# MainBoard_Motor1.net
KiCad netlist of a schematic drawn in Altium Designer
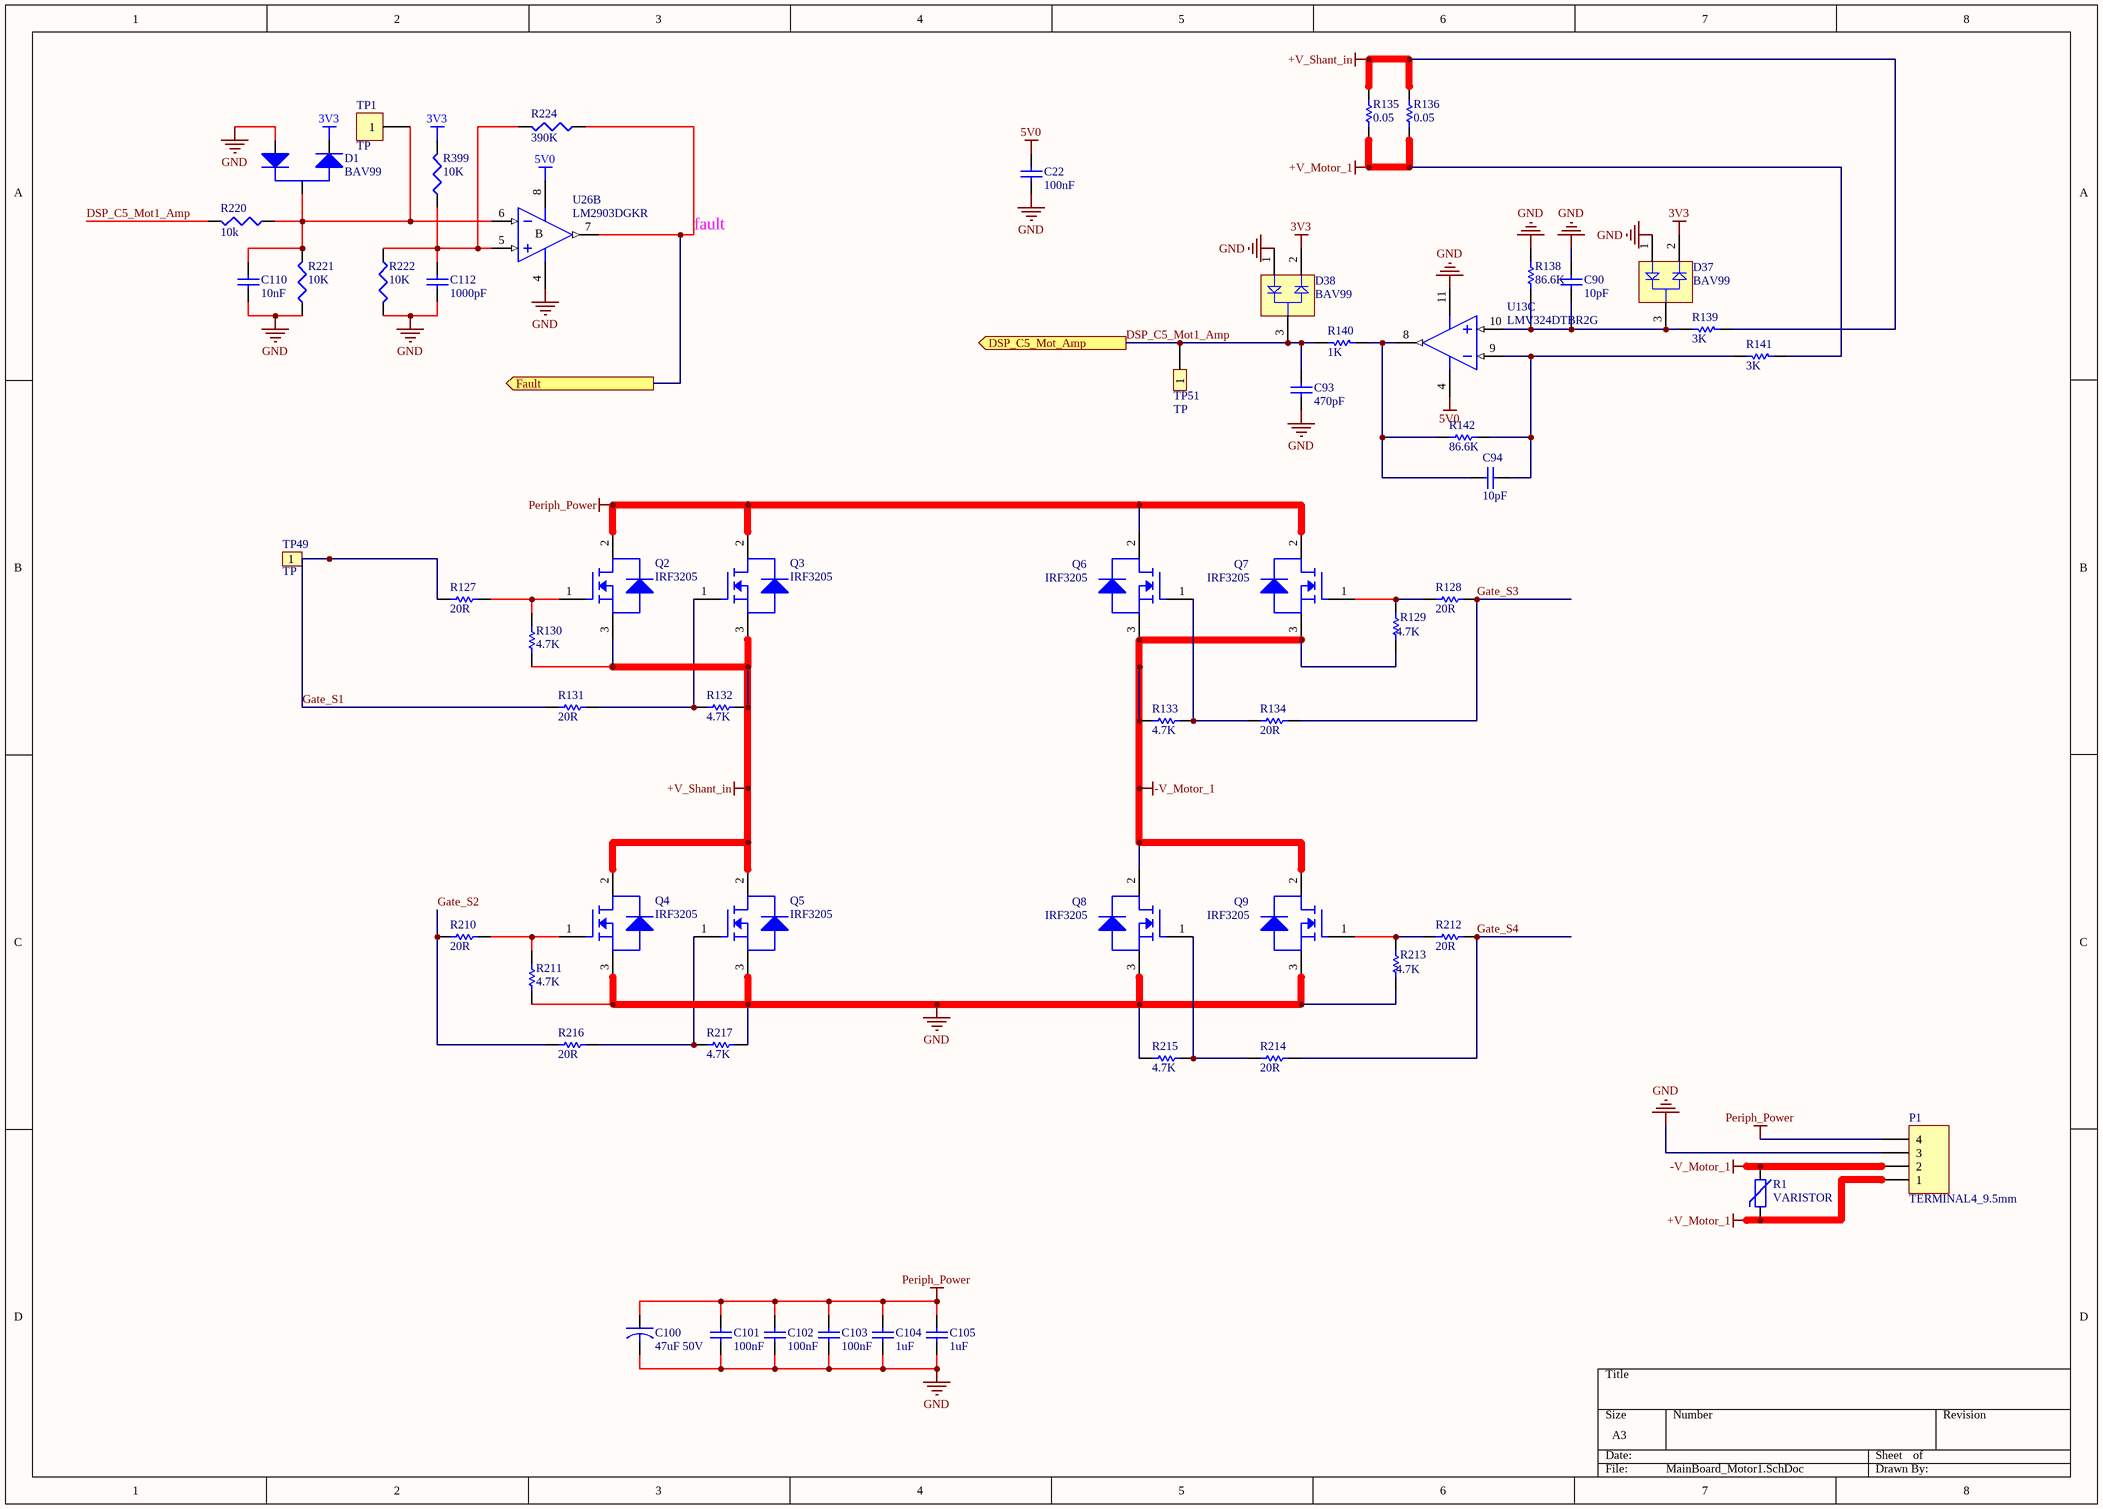
[diagram p0: MainBoard_Motor1.SchDoc]

(export (version "E")
  (design (tool "Eeschema 10.0.6"))
  (components
    (comp (ref "C22")
      (value "100nF")
      (footprint "EVIDC:C0603")
      (description "Ceramic Chip Capacitor - Standard")
      (fields
        (field (name "MANUFACTURER") "Yageo")
        (field (name "MFR PART NO") "CC0603KPX7R9BB104")
        (field (name "PUBLISHER") "Altium Limited")
      )
      (libsource (lib "KEMET Chip Capacitor") (part "C0402"))
    )
    (comp (ref "C90")
      (value "10pF")
      (footprint "EVIDC:C0603")
      (description "Cap_10pF_5%_C0G_50V_0603")
      (fields (field (name "MANUFACTURER") "Yageo") (field (name "MFR PART NO") "CC0603JRNPO9BN510"))
      (libsource (lib "EVIDC") (part "Cap_510pF_50V_0603"))
    )
    (comp (ref "C93")
      (value "470pF")
      (footprint "EVIDC:C0603")
      (description "Cap_470pF_5%_C0G_50V_0603")
      (fields (field (name "MFR PART NO") "CC0603JRNPO9BN471") (field (name "MANUFACTURER") "Yageo"))
      (libsource (lib "EVIDC") (part "Cap_470pF_50V_0603"))
    )
    (comp (ref "C94")
      (value "10pF")
      (footprint "C0603")
      (description "Cap_10pF_5%_C0G_50V_0603")
      (fields (field (name "MANUFACTURER") "Yageo") (field (name "MFR PART NO") "CC0603JRNPO9BN510"))
      (libsource (lib "EVIDC") (part "Cap_510pF_50V_0603"))
    )
    (comp (ref "C100")
      (value "47uF 50V")
      (footprint "RB-SGF-6.3MM")
      (description "Cap_47uF 50V_Pitch2.5mm")
      (fields (field (name "MFR PART NO") "ERS1HM470E11OT") (field (name "MANUFACTURER") "AIHUA"))
      (libsource (lib "EVIDC") (part "Cap_47uF 50V_EL_6.3mm"))
    )
    (comp (ref "C101")
      (value "100nF")
      (footprint "EVIDC:C0805")
      (description "Cap_100nF_5%_X7R_50V_0805")
      (fields (field (name "MANUFACTURER") "VISHAY") (field (name "MFR PART NO") "VJ0805Y104JXAAT"))
      (libsource (lib "EVIDC") (part "Cap_100nF_50V_0805"))
    )
    (comp (ref "C102")
      (value "100nF")
      (footprint "EVIDC:C0805")
      (description "Cap_100nF_5%_X7R_50V_0805")
      (fields (field (name "MANUFACTURER") "VISHAY") (field (name "MFR PART NO") "VJ0805Y104JXAAT"))
      (libsource (lib "EVIDC") (part "Cap_100nF_50V_0805"))
    )
    (comp (ref "C103")
      (value "100nF")
      (footprint "EVIDC:C0805")
      (description "Cap_100nF_5%_X7R_50V_0805")
      (fields (field (name "MANUFACTURER") "VISHAY") (field (name "MFR PART NO") "VJ0805Y104JXAAT"))
      (libsource (lib "EVIDC") (part "Cap_100nF_50V_0805"))
    )
    (comp (ref "C104")
      (value "1uF")
      (footprint "EVIDC:C0805")
      (description "Cap_1uF_20%_X5R_50V_0805")
      (fields (field (name "MFR PART NO") "UMK212BJ105MGHT") (field (name "MANUFACTURER") "Taiyo Yuden"))
      (libsource (lib "EVIDC") (part "Cap_1uF_50V_0805"))
    )
    (comp (ref "C105")
      (value "1uF")
      (footprint "EVIDC:C0805")
      (description "Cap_1uF_20%_X5R_50V_0805")
      (fields (field (name "MFR PART NO") "UMK212BJ105MGHT") (field (name "MANUFACTURER") "Taiyo Yuden"))
      (libsource (lib "EVIDC") (part "Cap_1uF_50V_0805"))
    )
    (comp (ref "C110")
      (value "10nF")
      (footprint "0603-C-PW")
      (description "CAP CER 10000PF 50V X7R 0603")
      (fields
        (field (name "MANUFACTURER") "Yageo")
        (field (name "MFR PART NO") "AC0603KPX7R9BB103")
        (field (name "PUBLISHER") "Altium Limited")
      )
      (libsource (lib "Miscellaneous Devices") (part "Cap"))
    )
    (comp (ref "C112")
      (value "1000pF")
      (footprint "0603-C-PW")
      (description "CAP CER 1000PF 50V X7R 0603")
      (fields
        (field (name "MANUFACTURER") "Yageo")
        (field (name "MFR PART NO") "CC0603KRX7R9BB102")
        (field (name "PUBLISHER") "Altium Limited")
      )
      (libsource (lib "Miscellaneous Devices") (part "Cap"))
    )
    (comp (ref "D1")
      (value "BAV99")
      (footprint "SOT-23-PW")
      (description "DIODE ARRAY GP 100V 215MA SOT23")
      (fields (field (name "MANUFACTURER") "Nexperia") (field (name "MFR PART NO") "BAV99,215"))
      (libsource (lib "PW232301036") (part "BAV99"))
    )
    (comp (ref "D37")
      (value "BAV99")
      (footprint "EVIDC:SOT-23")
      (description "Dِiode_BAV99_A7W_SOT23")
      (fields (field (name "MANUFACTURER") "Diode Incorporated") (field (name "MFR PART NO") "BAV99-7-F"))
      (libsource (lib "Infineon Transistor & Diode") (part "BAV99"))
    )
    (comp (ref "D38")
      (value "BAV99")
      (footprint "EVIDC:SOT-23")
      (description "Dِiode_BAV99_A7W_SOT23")
      (fields (field (name "MANUFACTURER") "Diode Incorporated") (field (name "MFR PART NO") "BAV99-7-F"))
      (libsource (lib "Infineon Transistor & Diode") (part "BAV99"))
    )
    (comp (ref "P1")
      (value "TERMINAL4_9.5mm")
      (footprint "Footprint_950322:Terminal 9.5mm_4")
      (description "T44-9.5mm_4")
      (fields (field (name "MANUFACTURER") "Cixi Kefa Elec") (field (name "MFR PART NO") "KF45C-9-5-4P"))
      (libsource (lib "SolarPanelCleaner_MainBoard_V1.1") (part "TERMINAL4_9.5mm"))
    )
    (comp (ref "Q2")
      (value "IRF3205")
      (footprint "2PH4888A00:TO-220")
      (description "MOSFET N-CHANNEL_ 55V_ TO-220")
      (fields (field (name "MANUFACTURER") "International Rectifier"))
      (libsource (lib "2PH4888A00") (part "MOS_IRF3205"))
    )
    (comp (ref "Q3")
      (value "IRF3205")
      (footprint "2PH4888A00:TO-220")
      (description "MOSFET N-CHANNEL_ 55V_ TO-220")
      (fields (field (name "MANUFACTURER") "International Rectifier"))
      (libsource (lib "2PH4888A00") (part "MOS_IRF3205"))
    )
    (comp (ref "Q4")
      (value "IRF3205")
      (footprint "2PH4888A00:TO-220")
      (description "MOSFET N-CHANNEL_ 55V_ TO-220")
      (fields (field (name "MANUFACTURER") "International Rectifier"))
      (libsource (lib "2PH4888A00") (part "MOS_IRF3205"))
    )
    (comp (ref "Q5")
      (value "IRF3205")
      (footprint "2PH4888A00:TO-220")
      (description "MOSFET N-CHANNEL_ 55V_ TO-220")
      (fields (field (name "MANUFACTURER") "International Rectifier"))
      (libsource (lib "2PH4888A00") (part "MOS_IRF3205"))
    )
    (comp (ref "Q6")
      (value "IRF3205")
      (footprint "2PH4888A00:TO-220")
      (description "MOSFET N-CHANNEL_ 55V_ TO-220")
      (fields (field (name "MANUFACTURER") "International Rectifier"))
      (libsource (lib "2PH4888A00") (part "MOS_IRF3205"))
    )
    (comp (ref "Q7")
      (value "IRF3205")
      (footprint "2PH4888A00:TO-220")
      (description "MOSFET N-CHANNEL_ 55V_ TO-220")
      (fields (field (name "MANUFACTURER") "International Rectifier"))
      (libsource (lib "2PH4888A00") (part "MOS_IRF3205"))
    )
    (comp (ref "Q8")
      (value "IRF3205")
      (footprint "2PH4888A00:TO-220")
      (description "MOSFET N-CHANNEL_ 55V_ TO-220")
      (fields (field (name "MANUFACTURER") "International Rectifier"))
      (libsource (lib "2PH4888A00") (part "MOS_IRF3205"))
    )
    (comp (ref "Q9")
      (value "IRF3205")
      (footprint "2PH4888A00:TO-220")
      (description "MOSFET N-CHANNEL_ 55V_ TO-220")
      (fields (field (name "MANUFACTURER") "International Rectifier"))
      (libsource (lib "2PH4888A00") (part "MOS_IRF3205"))
    )
    (comp (ref "R1")
      (value "VARISTOR")
      (footprint "2PH4888A00:VARISTOR")
      (description "35V 2cm")
      (fields (field (name "MANUFACTURER") "TDK Epcos") (field (name "MFR PART NO") "B72220S0350K101"))
      (libsource (lib "2PH4888A00") (part "VARISTOR"))
    )
    (comp (ref "R127")
      (value "20R")
      (footprint "EVIDC:R1206")
      (description "Res_20R_1%_0.25W_1206")
      (fields (field (name "MANUFACTURER") "Yageo") (field (name "MFR PART NO") "RC1206FR-0720RL"))
      (libsource (lib "EVIDC") (part "Res_20R_1206"))
    )
    (comp (ref "R128")
      (value "20R")
      (footprint "EVIDC:R1206")
      (description "Res_20R_1%_0.25W_1206")
      (fields (field (name "MANUFACTURER") "Yageo") (field (name "MFR PART NO") "RC1206FR-0720RL"))
      (libsource (lib "EVIDC") (part "Res_20R_1206"))
    )
    (comp (ref "R129")
      (value "4.7K")
      (footprint "EVIDC:R0805")
      (description "Res_4.7K_1%_0805")
      (fields (field (name "MANUFACTURER") "Yageo") (field (name "MFR PART NO") "RC0805FR-074K7L"))
      (libsource (lib "EVIDC") (part "Res_4.7K_0805"))
    )
    (comp (ref "R130")
      (value "4.7K")
      (footprint "EVIDC:R0805")
      (description "Res_4.7K_1%_0805")
      (fields (field (name "MANUFACTURER") "Yageo") (field (name "MFR PART NO") "RC0805FR-074K7L"))
      (libsource (lib "EVIDC") (part "Res_4.7K_0805"))
    )
    (comp (ref "R131")
      (value "20R")
      (footprint "EVIDC:R1206")
      (description "Res_20R_1%_0.25W_1206")
      (fields (field (name "MANUFACTURER") "Yageo") (field (name "MFR PART NO") "RC1206FR-0720RL"))
      (libsource (lib "EVIDC") (part "Res_20R_1206"))
    )
    (comp (ref "R132")
      (value "4.7K")
      (footprint "EVIDC:R0805")
      (description "Res_4.7K_1%_0805")
      (fields (field (name "MANUFACTURER") "Yageo") (field (name "MFR PART NO") "RC0805FR-074K7L"))
      (libsource (lib "EVIDC") (part "Res_4.7K_0805"))
    )
    (comp (ref "R133")
      (value "4.7K")
      (footprint "EVIDC:R0805")
      (description "Res_4.7K_1%_0805")
      (fields (field (name "MANUFACTURER") "Yageo") (field (name "MFR PART NO") "RC0805FR-074K7L"))
      (libsource (lib "EVIDC") (part "Res_4.7K_0805"))
    )
    (comp (ref "R134")
      (value "20R")
      (footprint "EVIDC:R1206")
      (description "Res_20R_1%_0.25W_1206")
      (fields (field (name "MANUFACTURER") "Yageo") (field (name "MFR PART NO") "RC1206FR-0720RL"))
      (libsource (lib "EVIDC") (part "Res_20R_1206"))
    )
    (comp (ref "R135")
      (value "0.05")
      (footprint "2PH4888A00:2512")
      (description "Res_0.05_1%_2512")
      (fields (field (name "MANUFACTURER") "Bourns Inc.") (field (name "MFR PART NO") "CRA2512-FZ-R050ELF"))
      (libsource (lib "2PH4888A00") (part "Res_0.05_2512"))
    )
    (comp (ref "R136")
      (value "0.05")
      (footprint "2PH4888A00:2512")
      (description "Res_0.05_1%_2512")
      (fields (field (name "MANUFACTURER") "Bourns Inc.") (field (name "MFR PART NO") "CRA2512-FZ-R050ELF"))
      (libsource (lib "2PH4888A00") (part "Res_0.05_2512"))
    )
    (comp (ref "R138")
      (value "86.6K")
      (footprint "R0603")
      (description "Res_86.6K_1%_0603")
      (fields (field (name "MANUFACTURER") "Yageo") (field (name "MFR PART NO") "AC0603FR-0786K6L"))
      (libsource (lib "2PH4888A00") (part "Res_86.6K_0603"))
    )
    (comp (ref "R139")
      (value "3K")
      (footprint "R0603")
      (description "Res_3K_1%_0603")
      (fields (field (name "MANUFACTURER") "Yageo") (field (name "MFR PART NO") "RC0603FR-073KL"))
      (libsource (lib "EVIDC") (part "Res_3K_0603"))
    )
    (comp (ref "R140")
      (value "1K")
      (footprint "EVIDC:R0603")
      (description "RES SMD 1K OHM 1% 1/10W 0603")
      (fields
        (field (name "MANUFACTURER") "Yageo")
        (field (name "MFR PART NO") "RC0603FR-071KL")
        (field (name "PUBLISHER") "Altium Limited")
      )
      (libsource (lib "Panasonic Resistor") (part "ERAV"))
    )
    (comp (ref "R141")
      (value "3K")
      (footprint "R0603")
      (description "Res_3K_1%_0603")
      (fields (field (name "MANUFACTURER") "Yageo") (field (name "MFR PART NO") "RC0603FR-073KL"))
      (libsource (lib "EVIDC") (part "Res_3K_0603"))
    )
    (comp (ref "R142")
      (value "86.6K")
      (footprint "R0603")
      (description "Res_86.6K_1%_0603")
      (fields (field (name "MANUFACTURER") "Yageo") (field (name "MFR PART NO") "AC0603FR-0786K6L"))
      (libsource (lib "2PH4888A00") (part "Res_86.6K_0603"))
    )
    (comp (ref "R210")
      (value "20R")
      (footprint "EVIDC:R1206")
      (description "Res_20R_1%_0.25W_1206")
      (fields (field (name "MANUFACTURER") "Yageo") (field (name "MFR PART NO") "RC1206FR-0720RL"))
      (libsource (lib "EVIDC") (part "Res_20R_1206"))
    )
    (comp (ref "R211")
      (value "4.7K")
      (footprint "EVIDC:R0805")
      (description "Res_4.7K_1%_0805")
      (fields (field (name "MANUFACTURER") "Yageo") (field (name "MFR PART NO") "RC0805FR-074K7L"))
      (libsource (lib "EVIDC") (part "Res_4.7K_0805"))
    )
    (comp (ref "R212")
      (value "20R")
      (footprint "EVIDC:R1206")
      (description "Res_20R_1%_0.25W_1206")
      (fields (field (name "MANUFACTURER") "Yageo") (field (name "MFR PART NO") "RC1206FR-0720RL"))
      (libsource (lib "EVIDC") (part "Res_20R_1206"))
    )
    (comp (ref "R213")
      (value "4.7K")
      (footprint "EVIDC:R0805")
      (description "Res_4.7K_1%_0805")
      (fields (field (name "MANUFACTURER") "Yageo") (field (name "MFR PART NO") "RC0805FR-074K7L"))
      (libsource (lib "EVIDC") (part "Res_4.7K_0805"))
    )
    (comp (ref "R214")
      (value "20R")
      (footprint "EVIDC:R1206")
      (description "Res_20R_1%_0.25W_1206")
      (fields (field (name "MANUFACTURER") "Yageo") (field (name "MFR PART NO") "RC1206FR-0720RL"))
      (libsource (lib "EVIDC") (part "Res_20R_1206"))
    )
    (comp (ref "R215")
      (value "4.7K")
      (footprint "EVIDC:R0805")
      (description "Res_4.7K_1%_0805")
      (fields (field (name "MANUFACTURER") "Yageo") (field (name "MFR PART NO") "RC0805FR-074K7L"))
      (libsource (lib "EVIDC") (part "Res_4.7K_0805"))
    )
    (comp (ref "R216")
      (value "20R")
      (footprint "EVIDC:R1206")
      (description "Res_20R_1%_0.25W_1206")
      (fields (field (name "MANUFACTURER") "Yageo") (field (name "MFR PART NO") "RC1206FR-0720RL"))
      (libsource (lib "EVIDC") (part "Res_20R_1206"))
    )
    (comp (ref "R217")
      (value "4.7K")
      (footprint "EVIDC:R0805")
      (description "Res_4.7K_1%_0805")
      (fields (field (name "MANUFACTURER") "Yageo") (field (name "MFR PART NO") "RC0805FR-074K7L"))
      (libsource (lib "EVIDC") (part "Res_4.7K_0805"))
    )
    (comp (ref "R220")
      (value "10k")
      (footprint "0603-R-PW")
      (description "RES SMD 47K OHM 1% 1/10W 0603")
      (fields (field (name "MANUFACTURER") "Yageo") (field (name "MFR PART NO") "RC0603FR-0747KL"))
      (libsource (lib "PW232301036") (part "RES1"))
    )
    (comp (ref "R221")
      (value "10K")
      (footprint "0603-R-PW")
      (description "RES SMD 3.9K OHM 1% 1/10W 0603")
      (fields (field (name "MANUFACTURER") "Yageo") (field (name "MFR PART NO") "RC0603FR-073K9L"))
      (libsource (lib "PW232301036") (part "RES1"))
    )
    (comp (ref "R222")
      (value "10K")
      (footprint "0402-R-PW")
      (description "RES SMD 11K OHM 1% 1/16W 0402")
      (fields (field (name "MANUFACTURER") "Yageo") (field (name "MFR PART NO") "RC0402FR-0711KL"))
      (libsource (lib "PW232301036") (part "RES1"))
    )
    (comp (ref "R224")
      (value "390K")
      (footprint "0603-R-PW")
      (description "Res Thick Film 0603 390K Ohm 1% 0.1W")
      (fields (field (name "MANUFACTURER") "Yageo") (field (name "MFR PART NO") "AC0603FR-07390KL"))
      (libsource (lib "PW232301036") (part "RES1"))
    )
    (comp (ref "R399")
      (value "10K")
      (footprint "0603-R-PW")
      (description "RES, THICK FILM, 4K7, 1%, 0.1W, 0603")
      (fields (field (name "MANUFACTURER") "Yageo") (field (name "MFR PART NO") "RC0603FR-134K7L"))
      (libsource (lib "PW232301036") (part "RES1"))
    )
    (comp (ref "TP1")
      (value "TP")
      (footprint "TP-SMD-1MM")
      (description "Header, 1-Pin")
      (fields (field (name "PUBLISHER") "Altium Limited"))
      (libsource (lib "RESCUE-VER001") (part "Header 1"))
    )
    (comp (ref "TP49")
      (value "TP")
      (footprint "2PH4888A00:TP_1mm")
      (description "TEST-POINT")
      (fields (field (name "PUBLISHER") "Altium Limited"))
      (libsource (lib "2PH4888A00") (part "TEST-POINT"))
    )
    (comp (ref "TP51")
      (value "TP")
      (footprint "2PH4888A00:TP_1mm")
      (description "TEST-POINT")
      (fields (field (name "PUBLISHER") "Altium Limited"))
      (libsource (lib "") (part "TEST-POINT_1"))
    )
    (comp (ref "U13")
      (value "LMV324DTBR2G")
      (footprint "EVIDC:SO-14")
      (description "IC_OpAmp_Quad_TSSOP-14")
      (fields (field (name "MANUFACTURER") "On Semiconductor"))
      (libsource (lib "ON Semi Signal Management Operational Amplifiers") (part "LMV324DTBR2G"))
    )
    (comp (ref "U26")
      (value "LM2903DGKR")
      (footprint "TSSOP_8-PW")
      (description "IC DUAL DIFF COMPARATOR 8VSSOP")
      (fields (field (name "MANUFACTURER") "Texas Instruments") (field (name "PUBLISHER") "Altium Limited"))
      (libsource (lib "Controller Board") (part "LM2903DGKR"))
    )
  )
  (nets
    (net (code "1") (name "+V_Motor_1") (class "Default")
      (node (ref "P1") (pin "1") (pinfunction "1_1") (pintype "passive"))
      (node (ref "R1") (pin "2") (pinfunction "2_2") (pintype "passive"))
      (node (ref "R135") (pin "2") (pinfunction "2_2") (pintype "passive"))
      (node (ref "R136") (pin "2") (pinfunction "2_2") (pintype "passive"))
      (node (ref "R141") (pin "1") (pinfunction "1_1") (pintype "passive"))
    )
    (net (code "2") (name "+V_Shant_in") (class "Default")
      (node (ref "Q2") (pin "3") (pinfunction "S_3") (pintype "passive"))
      (node (ref "Q3") (pin "3") (pinfunction "S_3") (pintype "passive"))
      (node (ref "Q4") (pin "2") (pinfunction "D_2") (pintype "passive"))
      (node (ref "Q5") (pin "2") (pinfunction "D_2") (pintype "passive"))
      (node (ref "R130") (pin "1") (pinfunction "1_1") (pintype "passive"))
      (node (ref "R132") (pin "1") (pinfunction "1_1") (pintype "passive"))
      (node (ref "R135") (pin "1") (pinfunction "1_1") (pintype "passive"))
      (node (ref "R136") (pin "1") (pinfunction "1_1") (pintype "passive"))
      (node (ref "R139") (pin "1") (pinfunction "1_1") (pintype "passive"))
    )
    (net (code "3") (name "-V_Motor_1") (class "Default")
      (node (ref "P1") (pin "2") (pinfunction "2_2") (pintype "passive"))
      (node (ref "Q6") (pin "3") (pinfunction "S_3") (pintype "passive"))
      (node (ref "Q7") (pin "3") (pinfunction "S_3") (pintype "passive"))
      (node (ref "Q8") (pin "2") (pinfunction "D_2") (pintype "passive"))
      (node (ref "Q9") (pin "2") (pinfunction "D_2") (pintype "passive"))
      (node (ref "R1") (pin "1") (pinfunction "1_1") (pintype "passive"))
      (node (ref "R129") (pin "1") (pinfunction "1_1") (pintype "passive"))
      (node (ref "R133") (pin "2") (pinfunction "2_2") (pintype "passive"))
    )
    (net (code "4") (name "/DSP_C5_Mot1_Amp") (class "Default")
      (node (ref "C93") (pin "2") (pinfunction "2_2") (pintype "passive"))
      (node (ref "D38") (pin "3") (pinfunction "C_3") (pintype "passive"))
      (node (ref "R140") (pin "1") (pinfunction "1_1") (pintype "passive"))
      (node (ref "R220") (pin "2") (pinfunction "2_2") (pintype "passive"))
      (node (ref "TP51") (pin "1") (pinfunction "1_1") (pintype "passive"))
    )
    (net (code "5") (name "/Gate_S1") (class "Default")
      (node (ref "R127") (pin "1") (pinfunction "1_1") (pintype "passive"))
      (node (ref "R131") (pin "1") (pinfunction "1_1") (pintype "passive"))
      (node (ref "TP49") (pin "1") (pinfunction "1_1") (pintype "passive"))
    )
    (net (code "6") (name "/Gate_S2") (class "Default")
      (node (ref "R210") (pin "1") (pinfunction "1_1") (pintype "passive"))
      (node (ref "R216") (pin "1") (pinfunction "1_1") (pintype "passive"))
    )
    (net (code "7") (name "/Gate_S3") (class "Default")
      (node (ref "R128") (pin "2") (pinfunction "2_2") (pintype "passive"))
      (node (ref "R134") (pin "2") (pinfunction "2_2") (pintype "passive"))
    )
    (net (code "8") (name "/Gate_S4") (class "Default")
      (node (ref "R212") (pin "2") (pinfunction "2_2") (pintype "passive"))
      (node (ref "R214") (pin "2") (pinfunction "2_2") (pintype "passive"))
    )
    (net (code "9") (name "/fault") (class "Default")
      (node (ref "R224") (pin "2") (pinfunction "2_2") (pintype "passive"))
      (node (ref "U26") (pin "7") (pinfunction "OUT_7") (pintype "output"))
    )
    (net (code "10") (name "3V3") (class "Default")
      (node (ref "D1") (pin "2") (pinfunction "K_2") (pintype "passive"))
      (node (ref "D37") (pin "2") (pinfunction "K2_2") (pintype "passive"))
      (node (ref "D38") (pin "2") (pinfunction "K2_2") (pintype "passive"))
      (node (ref "R399") (pin "2") (pinfunction "2_2") (pintype "passive"))
    )
    (net (code "11") (name "5V0") (class "Default")
      (node (ref "C22") (pin "2") (pinfunction "2_2") (pintype "passive"))
      (node (ref "U13") (pin "4") (pinfunction "V+_4") (pintype "power_in"))
      (node (ref "U26") (pin "8") (pinfunction "V+_8") (pintype "power_in"))
    )
    (net (code "12") (name "GND") (class "Default")
      (node (ref "C100") (pin "2") (pinfunction "2_2") (pintype "passive"))
      (node (ref "C101") (pin "1") (pinfunction "1_1") (pintype "passive"))
      (node (ref "C102") (pin "1") (pinfunction "1_1") (pintype "passive"))
      (node (ref "C103") (pin "1") (pinfunction "1_1") (pintype "passive"))
      (node (ref "C104") (pin "1") (pinfunction "1_1") (pintype "passive"))
      (node (ref "C105") (pin "1") (pinfunction "1_1") (pintype "passive"))
      (node (ref "C110") (pin "1") (pinfunction "1_1") (pintype "passive"))
      (node (ref "C112") (pin "1") (pinfunction "1_1") (pintype "passive"))
      (node (ref "C22") (pin "1") (pinfunction "1_1") (pintype "passive"))
      (node (ref "C90") (pin "2") (pinfunction "2_2") (pintype "passive"))
      (node (ref "C93") (pin "1") (pinfunction "1_1") (pintype "passive"))
      (node (ref "D1") (pin "1") (pinfunction "A_1") (pintype "passive"))
      (node (ref "D37") (pin "1") (pinfunction "A1_1") (pintype "passive"))
      (node (ref "D38") (pin "1") (pinfunction "A1_1") (pintype "passive"))
      (node (ref "P1") (pin "3") (pinfunction "3_3") (pintype "passive"))
      (node (ref "Q4") (pin "3") (pinfunction "S_3") (pintype "passive"))
      (node (ref "Q5") (pin "3") (pinfunction "S_3") (pintype "passive"))
      (node (ref "Q8") (pin "3") (pinfunction "S_3") (pintype "passive"))
      (node (ref "Q9") (pin "3") (pinfunction "S_3") (pintype "passive"))
      (node (ref "R138") (pin "2") (pinfunction "2_2") (pintype "passive"))
      (node (ref "R211") (pin "1") (pinfunction "1_1") (pintype "passive"))
      (node (ref "R213") (pin "1") (pinfunction "1_1") (pintype "passive"))
      (node (ref "R215") (pin "2") (pinfunction "2_2") (pintype "passive"))
      (node (ref "R217") (pin "1") (pinfunction "1_1") (pintype "passive"))
      (node (ref "R221") (pin "1") (pinfunction "1_1") (pintype "passive"))
      (node (ref "R222") (pin "1") (pinfunction "1_1") (pintype "passive"))
      (node (ref "U13") (pin "11") (pinfunction "V-_11") (pintype "power_in"))
      (node (ref "U26") (pin "4") (pinfunction "V-_4") (pintype "power_in"))
    )
    (net (code "13") (name "Net-(D1-AK)") (class "Default")
      (node (ref "C110") (pin "2") (pinfunction "2_2") (pintype "passive"))
      (node (ref "D1") (pin "3") (pinfunction "AK_3") (pintype "passive"))
      (node (ref "R220") (pin "1") (pinfunction "1_1") (pintype "passive"))
      (node (ref "R221") (pin "2") (pinfunction "2_2") (pintype "passive"))
      (node (ref "TP1") (pin "1") (pinfunction "1_1") (pintype "passive"))
      (node (ref "U26") (pin "6") (pinfunction "IN-_6") (pintype "input"))
    )
    (net (code "14") (name "Net-(D37-C)") (class "Default")
      (node (ref "C90") (pin "1") (pinfunction "1_1") (pintype "passive"))
      (node (ref "D37") (pin "3") (pinfunction "C_3") (pintype "passive"))
      (node (ref "R138") (pin "1") (pinfunction "1_1") (pintype "passive"))
      (node (ref "R139") (pin "2") (pinfunction "2_2") (pintype "passive"))
      (node (ref "U13") (pin "10") (pinfunction "INC+_10") (pintype "input"))
    )
    (net (code "15") (name "Net-(Q2-G)") (class "Default")
      (node (ref "Q2") (pin "1") (pinfunction "G_1") (pintype "passive"))
      (node (ref "R127") (pin "2") (pinfunction "2_2") (pintype "passive"))
      (node (ref "R130") (pin "2") (pinfunction "2_2") (pintype "passive"))
    )
    (net (code "16") (name "Net-(Q3-G)") (class "Default")
      (node (ref "Q3") (pin "1") (pinfunction "G_1") (pintype "passive"))
      (node (ref "R131") (pin "2") (pinfunction "2_2") (pintype "passive"))
      (node (ref "R132") (pin "2") (pinfunction "2_2") (pintype "passive"))
    )
    (net (code "17") (name "Net-(Q4-G)") (class "Default")
      (node (ref "Q4") (pin "1") (pinfunction "G_1") (pintype "passive"))
      (node (ref "R210") (pin "2") (pinfunction "2_2") (pintype "passive"))
      (node (ref "R211") (pin "2") (pinfunction "2_2") (pintype "passive"))
    )
    (net (code "18") (name "Net-(Q5-G)") (class "Default")
      (node (ref "Q5") (pin "1") (pinfunction "G_1") (pintype "passive"))
      (node (ref "R216") (pin "2") (pinfunction "2_2") (pintype "passive"))
      (node (ref "R217") (pin "2") (pinfunction "2_2") (pintype "passive"))
    )
    (net (code "19") (name "Net-(Q6-G)") (class "Default")
      (node (ref "Q6") (pin "1") (pinfunction "G_1") (pintype "passive"))
      (node (ref "R133") (pin "1") (pinfunction "1_1") (pintype "passive"))
      (node (ref "R134") (pin "1") (pinfunction "1_1") (pintype "passive"))
    )
    (net (code "20") (name "Net-(Q7-G)") (class "Default")
      (node (ref "Q7") (pin "1") (pinfunction "G_1") (pintype "passive"))
      (node (ref "R128") (pin "1") (pinfunction "1_1") (pintype "passive"))
      (node (ref "R129") (pin "2") (pinfunction "2_2") (pintype "passive"))
    )
    (net (code "21") (name "Net-(Q8-G)") (class "Default")
      (node (ref "Q8") (pin "1") (pinfunction "G_1") (pintype "passive"))
      (node (ref "R214") (pin "1") (pinfunction "1_1") (pintype "passive"))
      (node (ref "R215") (pin "1") (pinfunction "1_1") (pintype "passive"))
    )
    (net (code "22") (name "Net-(Q9-G)") (class "Default")
      (node (ref "Q9") (pin "1") (pinfunction "G_1") (pintype "passive"))
      (node (ref "R212") (pin "1") (pinfunction "1_1") (pintype "passive"))
      (node (ref "R213") (pin "2") (pinfunction "2_2") (pintype "passive"))
    )
    (net (code "23") (name "Net-(U13C-INC-)") (class "Default")
      (node (ref "C94") (pin "2") (pinfunction "2_2") (pintype "passive"))
      (node (ref "R141") (pin "2") (pinfunction "2_2") (pintype "passive"))
      (node (ref "R142") (pin "2") (pinfunction "2_2") (pintype "passive"))
      (node (ref "U13") (pin "9") (pinfunction "INC-_9") (pintype "input"))
    )
    (net (code "24") (name "Net-(U13C-OUTC)") (class "Default")
      (node (ref "C94") (pin "1") (pinfunction "1_1") (pintype "passive"))
      (node (ref "R140") (pin "2") (pinfunction "2_2") (pintype "passive"))
      (node (ref "R142") (pin "1") (pinfunction "1_1") (pintype "passive"))
      (node (ref "U13") (pin "8") (pinfunction "OUTC_8") (pintype "output"))
    )
    (net (code "25") (name "Net-(U26B-IN+)") (class "Default")
      (node (ref "C112") (pin "2") (pinfunction "2_2") (pintype "passive"))
      (node (ref "R222") (pin "2") (pinfunction "2_2") (pintype "passive"))
      (node (ref "R224") (pin "1") (pinfunction "1_1") (pintype "passive"))
      (node (ref "R399") (pin "1") (pinfunction "1_1") (pintype "passive"))
      (node (ref "U26") (pin "5") (pinfunction "IN+_5") (pintype "input"))
    )
    (net (code "26") (name "Periph_Power") (class "Default")
      (node (ref "C100") (pin "1") (pinfunction "1_1") (pintype "passive"))
      (node (ref "C101") (pin "2") (pinfunction "2_2") (pintype "passive"))
      (node (ref "C102") (pin "2") (pinfunction "2_2") (pintype "passive"))
      (node (ref "C103") (pin "2") (pinfunction "2_2") (pintype "passive"))
      (node (ref "C104") (pin "2") (pinfunction "2_2") (pintype "passive"))
      (node (ref "C105") (pin "2") (pinfunction "2_2") (pintype "passive"))
      (node (ref "P1") (pin "4") (pinfunction "4_4") (pintype "passive"))
      (node (ref "Q2") (pin "2") (pinfunction "D_2") (pintype "passive"))
      (node (ref "Q3") (pin "2") (pinfunction "D_2") (pintype "passive"))
      (node (ref "Q6") (pin "2") (pinfunction "D_2") (pintype "passive"))
      (node (ref "Q7") (pin "2") (pinfunction "D_2") (pintype "passive"))
    )
  )
)
